# A4a_ESP32_WiFi_BLE.net
KiCad netlist of a schematic drawn in EAGLE
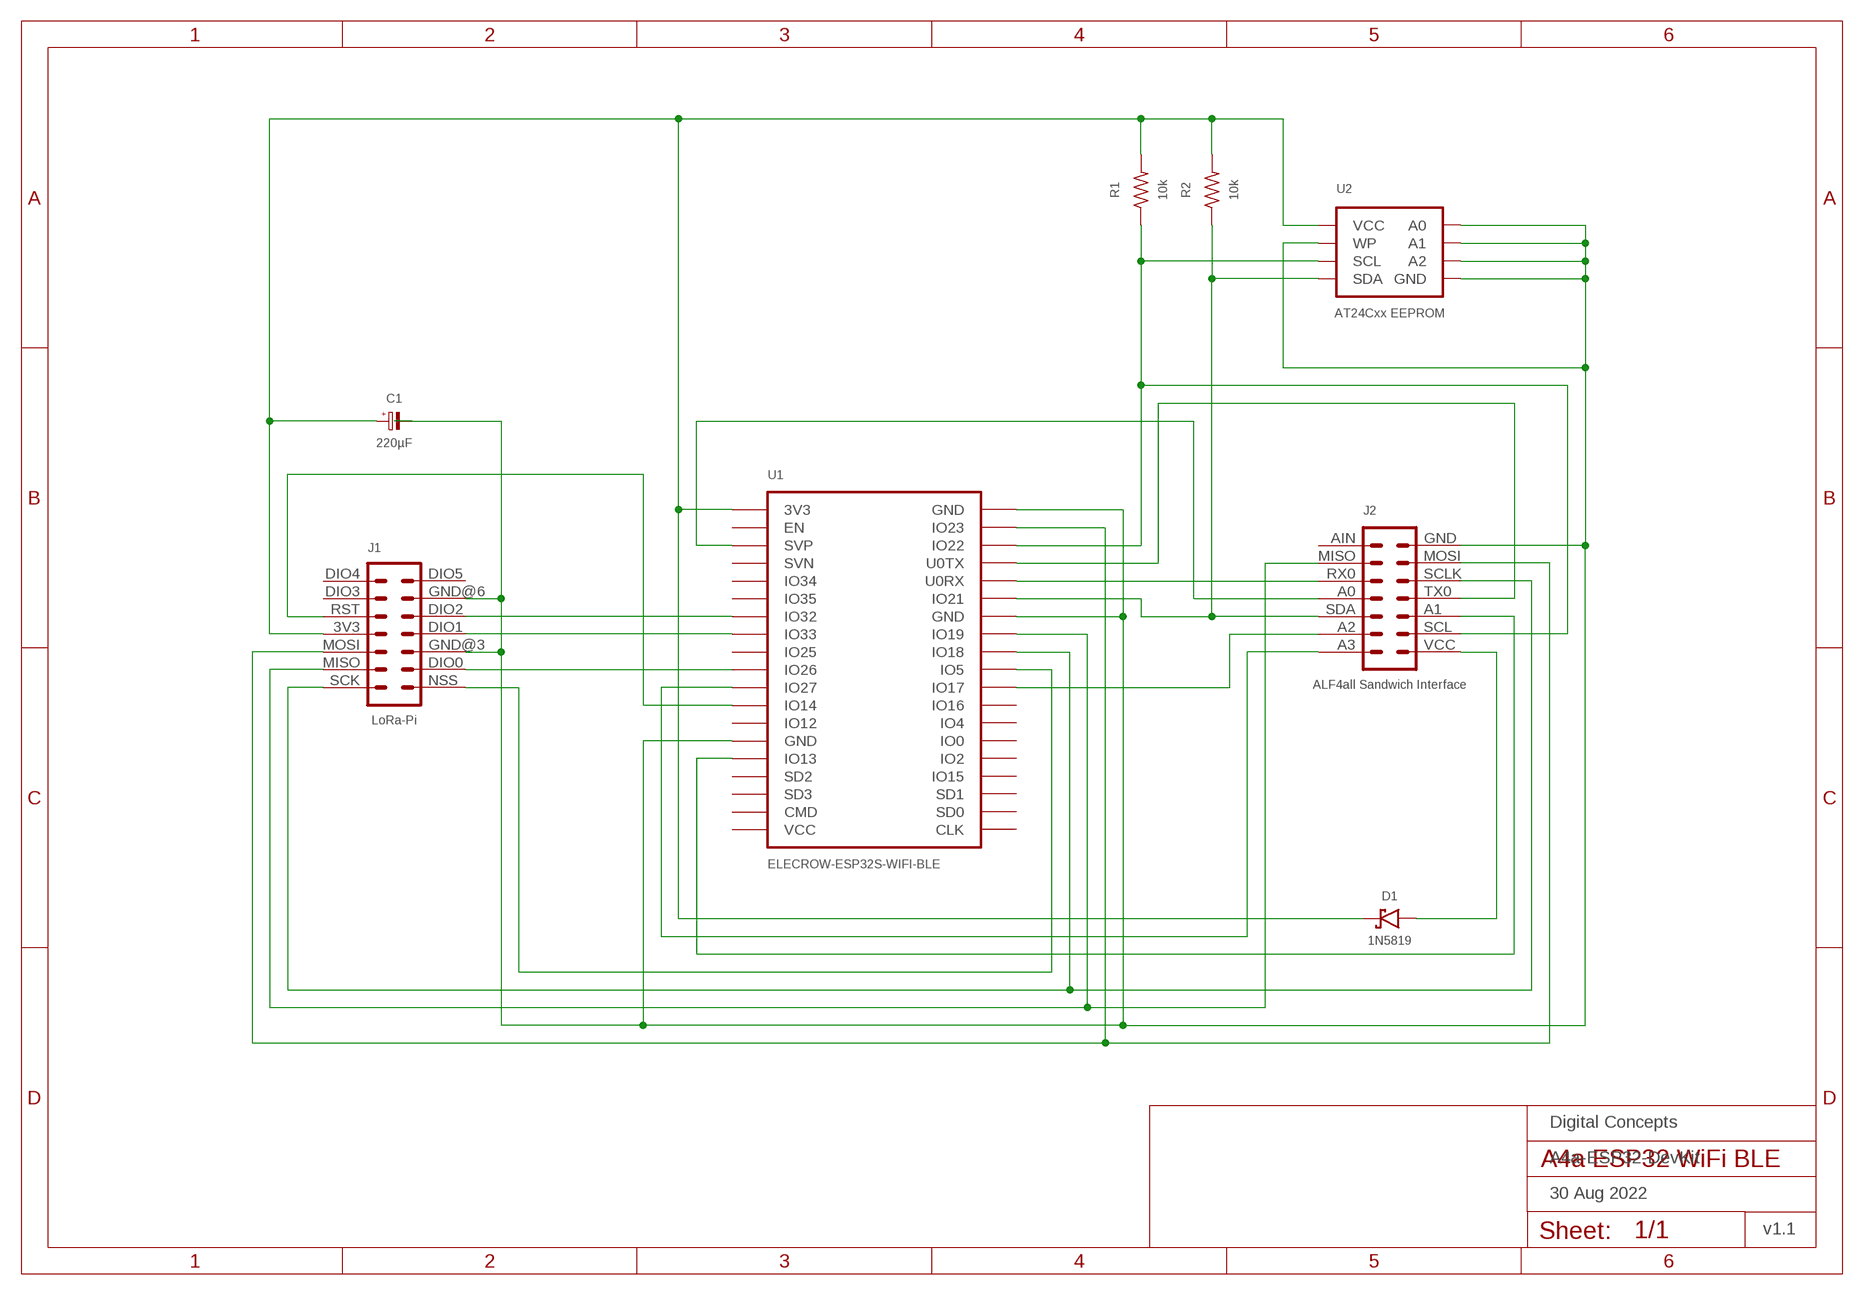
[diagram p0: schematic, sheet 1]

(export (version "E")
  (design (tool "Eeschema 10.0.6"))
  (components
    (comp (ref "C1")
      (value "220µF")
      (footprint "eagle-import:C3528-21")
      (libsource (lib "eagle-import") (part "CAPACITOR-3528-TANTALUM"))
    )
    (comp (ref "D1")
      (value "1N5819")
      (footprint "eagle-import:SOD-123")
      (libsource (lib "eagle-import") (part "DIODE-SCHOTTKY-1N5819"))
    )
    (comp (ref "J1")
      (value "LoRa-Pi")
      (footprint "eagle-import:RFM95W-PI")
      (libsource (lib "eagle-import") (part "RFM95W-PI-HEADER"))
    )
    (comp (ref "J2")
      (value "ALF4all Sandwich Interface")
      (footprint "eagle-import:CONN_2X7-ALF4ALL-PROCESSOR-B")
      (libsource (lib "eagle-import") (part "HEADER-2X7-ALF4ALL-PROCESSOR-B"))
    )
    (comp (ref "R1")
      (value "10k")
      (footprint "eagle-import:R0805")
      (libsource (lib "eagle-import") (part "RESISTORR0805"))
    )
    (comp (ref "R2")
      (value "10k")
      (footprint "eagle-import:R0805")
      (libsource (lib "eagle-import") (part "RESISTORR0805"))
    )
    (comp (ref "U1")
      (value "ELECROW-ESP32S-WIFI-BLE")
      (footprint "eagle-import:ELECROW-ESP32S-WIFI-BLE")
      (libsource (lib "eagle-import") (part "ELECROW-ESP32S-WIFI-BLE"))
    )
    (comp (ref "U2")
      (value "AT24Cxx EEPROM")
      (footprint "eagle-import:SOP-8")
      (libsource (lib "eagle-import") (part "AT24CXX-EEPROM"))
    )
  )
  (nets
    (net (code "1") (name "Net-(C1-+)") (class "Default")
      (node (ref "C1") (pin "1") (pinfunction "+_1") (pintype "passive"))
      (node (ref "D1") (pin "C") (pinfunction "C_C") (pintype "passive"))
      (node (ref "J1") (pin "3V3") (pinfunction "11_3V3") (pintype "passive"))
      (node (ref "R1") (pin "2") (pinfunction "2_2") (pintype "passive"))
      (node (ref "R2") (pin "2") (pinfunction "2_2") (pintype "passive"))
      (node (ref "U1") (pin "3V3") (pinfunction "3V3_3V3") (pintype "bidirectional"))
      (node (ref "U2") (pin "P$8") (pinfunction "VCC_P$8") (pintype "bidirectional"))
    )
    (net (code "2") (name "Net-(C1--)") (class "Default")
      (node (ref "C1") (pin "2") (pinfunction "-_2") (pintype "passive"))
      (node (ref "J1") (pin "GND@3") (pinfunction "3_GND@3") (pintype "passive"))
      (node (ref "J1") (pin "GND@6") (pinfunction "6_GND@6") (pintype "passive"))
      (node (ref "J2") (pin "GND") (pinfunction "7_GND") (pintype "passive"))
      (node (ref "U1") (pin "GND@13") (pinfunction "GND_GND@13") (pintype "bidirectional"))
      (node (ref "U1") (pin "GND@19") (pinfunction "GND_GND@19") (pintype "bidirectional"))
      (node (ref "U1") (pin "GND@33") (pinfunction "GND_GND@33") (pintype "bidirectional"))
      (node (ref "U2") (pin "P$1") (pinfunction "A0_P$1") (pintype "bidirectional"))
      (node (ref "U2") (pin "P$2") (pinfunction "A1_P$2") (pintype "bidirectional"))
      (node (ref "U2") (pin "P$3") (pinfunction "A2_P$3") (pintype "bidirectional"))
      (node (ref "U2") (pin "P$4") (pinfunction "GND_P$4") (pintype "bidirectional"))
      (node (ref "U2") (pin "P$7") (pinfunction "WP_P$7") (pintype "bidirectional"))
    )
    (net (code "3") (name "Net-(J1-1)") (class "Default")
      (node (ref "J1") (pin "NSS") (pinfunction "1_NSS") (pintype "passive"))
      (node (ref "U1") (pin "IO5") (pinfunction "IO5_IO5") (pintype "bidirectional"))
    )
    (net (code "4") (name "Net-(J1-2)") (class "Default")
      (node (ref "J1") (pin "DIO0") (pinfunction "2_DIO0") (pintype "passive"))
      (node (ref "U1") (pin "IO26") (pinfunction "IO26_IO26") (pintype "bidirectional"))
    )
    (net (code "5") (name "Net-(J1-4)") (class "Default")
      (node (ref "J1") (pin "DIO1") (pinfunction "4_DIO1") (pintype "passive"))
      (node (ref "U1") (pin "IO33") (pinfunction "IO33_IO33") (pintype "bidirectional"))
    )
    (net (code "6") (name "Net-(J1-5)") (class "Default")
      (node (ref "J1") (pin "DIO2") (pinfunction "5_DIO2") (pintype "passive"))
      (node (ref "U1") (pin "IO32") (pinfunction "IO32_IO32") (pintype "bidirectional"))
    )
    (net (code "7") (name "Net-(J1-10)") (class "Default")
      (node (ref "J1") (pin "RST") (pinfunction "10_RST") (pintype "passive"))
      (node (ref "U1") (pin "IO14") (pinfunction "IO14_IO14") (pintype "bidirectional"))
    )
    (net (code "8") (name "Net-(J1-12)") (class "Default")
      (node (ref "J1") (pin "MOSI") (pinfunction "12_MOSI") (pintype "passive"))
      (node (ref "J2") (pin "MOSI") (pinfunction "6_MOSI") (pintype "passive"))
      (node (ref "U1") (pin "IO23") (pinfunction "IO23_IO23") (pintype "bidirectional"))
    )
    (net (code "9") (name "Net-(J1-13)") (class "Default")
      (node (ref "J1") (pin "MISO") (pinfunction "13_MISO") (pintype "passive"))
      (node (ref "J2") (pin "MISO") (pinfunction "9_MISO") (pintype "passive"))
      (node (ref "U1") (pin "IO19") (pinfunction "IO19_IO19") (pintype "bidirectional"))
    )
    (net (code "10") (name "Net-(J1-14)") (class "Default")
      (node (ref "J1") (pin "SCK") (pinfunction "14_SCK") (pintype "passive"))
      (node (ref "J2") (pin "SCLK") (pinfunction "5_SCLK") (pintype "passive"))
      (node (ref "U1") (pin "IO18") (pinfunction "IO18_IO18") (pintype "bidirectional"))
    )
    (net (code "11") (name "Net-(J2-1)") (class "Default")
      (node (ref "D1") (pin "A") (pinfunction "A_A") (pintype "passive"))
      (node (ref "J2") (pin "VCC") (pinfunction "1_VCC") (pintype "passive"))
    )
    (net (code "12") (name "Net-(J2-2)") (class "Default")
      (node (ref "J2") (pin "SCL") (pinfunction "2_SCL") (pintype "passive"))
      (node (ref "R1") (pin "1") (pinfunction "1_1") (pintype "passive"))
      (node (ref "U1") (pin "IO22") (pinfunction "IO22_IO22") (pintype "bidirectional"))
      (node (ref "U2") (pin "P$6") (pinfunction "SCL_P$6") (pintype "bidirectional"))
    )
    (net (code "13") (name "Net-(J2-3)") (class "Default")
      (node (ref "J2") (pin "A1") (pinfunction "3_A1") (pintype "passive"))
      (node (ref "U1") (pin "IO13") (pinfunction "IO13_IO13") (pintype "bidirectional"))
    )
    (net (code "14") (name "Net-(J2-4)") (class "Default")
      (node (ref "J2") (pin "TX0") (pinfunction "4_TX0") (pintype "passive"))
      (node (ref "U1") (pin "U0TX") (pinfunction "U0TX_U0TX") (pintype "bidirectional"))
    )
    (net (code "15") (name "Net-(J2-10)") (class "Default")
      (node (ref "J2") (pin "RX0") (pinfunction "10_RX0") (pintype "passive"))
      (node (ref "U1") (pin "U0RX") (pinfunction "U0RX_U0RX") (pintype "bidirectional"))
    )
    (net (code "16") (name "Net-(J2-11)") (class "Default")
      (node (ref "J2") (pin "A0") (pinfunction "11_A0") (pintype "passive"))
      (node (ref "U1") (pin "SVP") (pinfunction "SVP_SVP") (pintype "bidirectional"))
    )
    (net (code "17") (name "Net-(J2-12)") (class "Default")
      (node (ref "J2") (pin "SDA") (pinfunction "12_SDA") (pintype "passive"))
      (node (ref "R2") (pin "1") (pinfunction "1_1") (pintype "passive"))
      (node (ref "U1") (pin "IO21") (pinfunction "IO21_IO21") (pintype "bidirectional"))
      (node (ref "U2") (pin "P$5") (pinfunction "SDA_P$5") (pintype "bidirectional"))
    )
    (net (code "18") (name "Net-(J2-13)") (class "Default")
      (node (ref "J2") (pin "A2") (pinfunction "13_A2") (pintype "passive"))
      (node (ref "U1") (pin "IO17") (pinfunction "IO17_IO17") (pintype "bidirectional"))
    )
    (net (code "19") (name "Net-(J2-14)") (class "Default")
      (node (ref "J2") (pin "A3") (pinfunction "14_A3") (pintype "passive"))
      (node (ref "U1") (pin "IO27") (pinfunction "IO27_IO27") (pintype "bidirectional"))
    )
    (net (code "20") (name "unconnected-(J1-7-PadDIO5)") (class "Default")
      (node (ref "J1") (pin "DIO5") (pinfunction "7_DIO5") (pintype "passive"))
    )
    (net (code "21") (name "unconnected-(J1-8-PadDIO4)") (class "Default")
      (node (ref "J1") (pin "DIO4") (pinfunction "8_DIO4") (pintype "passive"))
    )
    (net (code "22") (name "unconnected-(J1-9-PadDIO3)") (class "Default")
      (node (ref "J1") (pin "DIO3") (pinfunction "9_DIO3") (pintype "passive"))
    )
    (net (code "23") (name "unconnected-(J2-8-PadAIN)") (class "Default")
      (node (ref "J2") (pin "AIN") (pinfunction "8_AIN") (pintype "passive"))
    )
    (net (code "24") (name "unconnected-(U1-PadCLK)") (class "Default")
      (node (ref "U1") (pin "CLK") (pinfunction "CLK_CLK") (pintype "bidirectional"))
    )
    (net (code "25") (name "unconnected-(U1-PadCMD)") (class "Default")
      (node (ref "U1") (pin "CMD") (pinfunction "CMD_CMD") (pintype "bidirectional"))
    )
    (net (code "26") (name "unconnected-(U1-PadEN)") (class "Default")
      (node (ref "U1") (pin "EN") (pinfunction "EN_EN") (pintype "bidirectional"))
    )
    (net (code "27") (name "unconnected-(U1-PadIO0)") (class "Default")
      (node (ref "U1") (pin "IO0") (pinfunction "IO0_IO0") (pintype "bidirectional"))
    )
    (net (code "28") (name "unconnected-(U1-PadIO2)") (class "Default")
      (node (ref "U1") (pin "IO2") (pinfunction "IO2_IO2") (pintype "bidirectional"))
    )
    (net (code "29") (name "unconnected-(U1-PadIO4)") (class "Default")
      (node (ref "U1") (pin "IO4") (pinfunction "IO4_IO4") (pintype "bidirectional"))
    )
    (net (code "30") (name "unconnected-(U1-PadIO12)") (class "Default")
      (node (ref "U1") (pin "IO12") (pinfunction "IO12_IO12") (pintype "bidirectional"))
    )
    (net (code "31") (name "unconnected-(U1-PadIO15)") (class "Default")
      (node (ref "U1") (pin "IO15") (pinfunction "IO15_IO15") (pintype "bidirectional"))
    )
    (net (code "32") (name "unconnected-(U1-PadIO16)") (class "Default")
      (node (ref "U1") (pin "IO16") (pinfunction "IO16_IO16") (pintype "bidirectional"))
    )
    (net (code "33") (name "unconnected-(U1-PadIO25)") (class "Default")
      (node (ref "U1") (pin "IO25") (pinfunction "IO25_IO25") (pintype "bidirectional"))
    )
    (net (code "34") (name "unconnected-(U1-PadIO34)") (class "Default")
      (node (ref "U1") (pin "IO34") (pinfunction "IO34_IO34") (pintype "bidirectional"))
    )
    (net (code "35") (name "unconnected-(U1-PadIO35)") (class "Default")
      (node (ref "U1") (pin "IO35") (pinfunction "IO35_IO35") (pintype "bidirectional"))
    )
    (net (code "36") (name "unconnected-(U1-PadSD0)") (class "Default")
      (node (ref "U1") (pin "SD0") (pinfunction "SD0_SD0") (pintype "bidirectional"))
    )
    (net (code "37") (name "unconnected-(U1-PadSD1)") (class "Default")
      (node (ref "U1") (pin "SD1") (pinfunction "SD1_SD1") (pintype "bidirectional"))
    )
    (net (code "38") (name "unconnected-(U1-PadSD2)") (class "Default")
      (node (ref "U1") (pin "SD2") (pinfunction "SD2_SD2") (pintype "bidirectional"))
    )
    (net (code "39") (name "unconnected-(U1-PadSD3)") (class "Default")
      (node (ref "U1") (pin "SD3") (pinfunction "SD3_SD3") (pintype "bidirectional"))
    )
    (net (code "40") (name "unconnected-(U1-PadSVN)") (class "Default")
      (node (ref "U1") (pin "SVN") (pinfunction "SVN_SVN") (pintype "bidirectional"))
    )
    (net (code "41") (name "unconnected-(U1-PadVCC)") (class "Default")
      (node (ref "U1") (pin "VCC") (pinfunction "VCC_VCC") (pintype "bidirectional"))
    )
  )
)
